# spi_cam.net
KiCad netlist of a schematic drawn in EAGLE
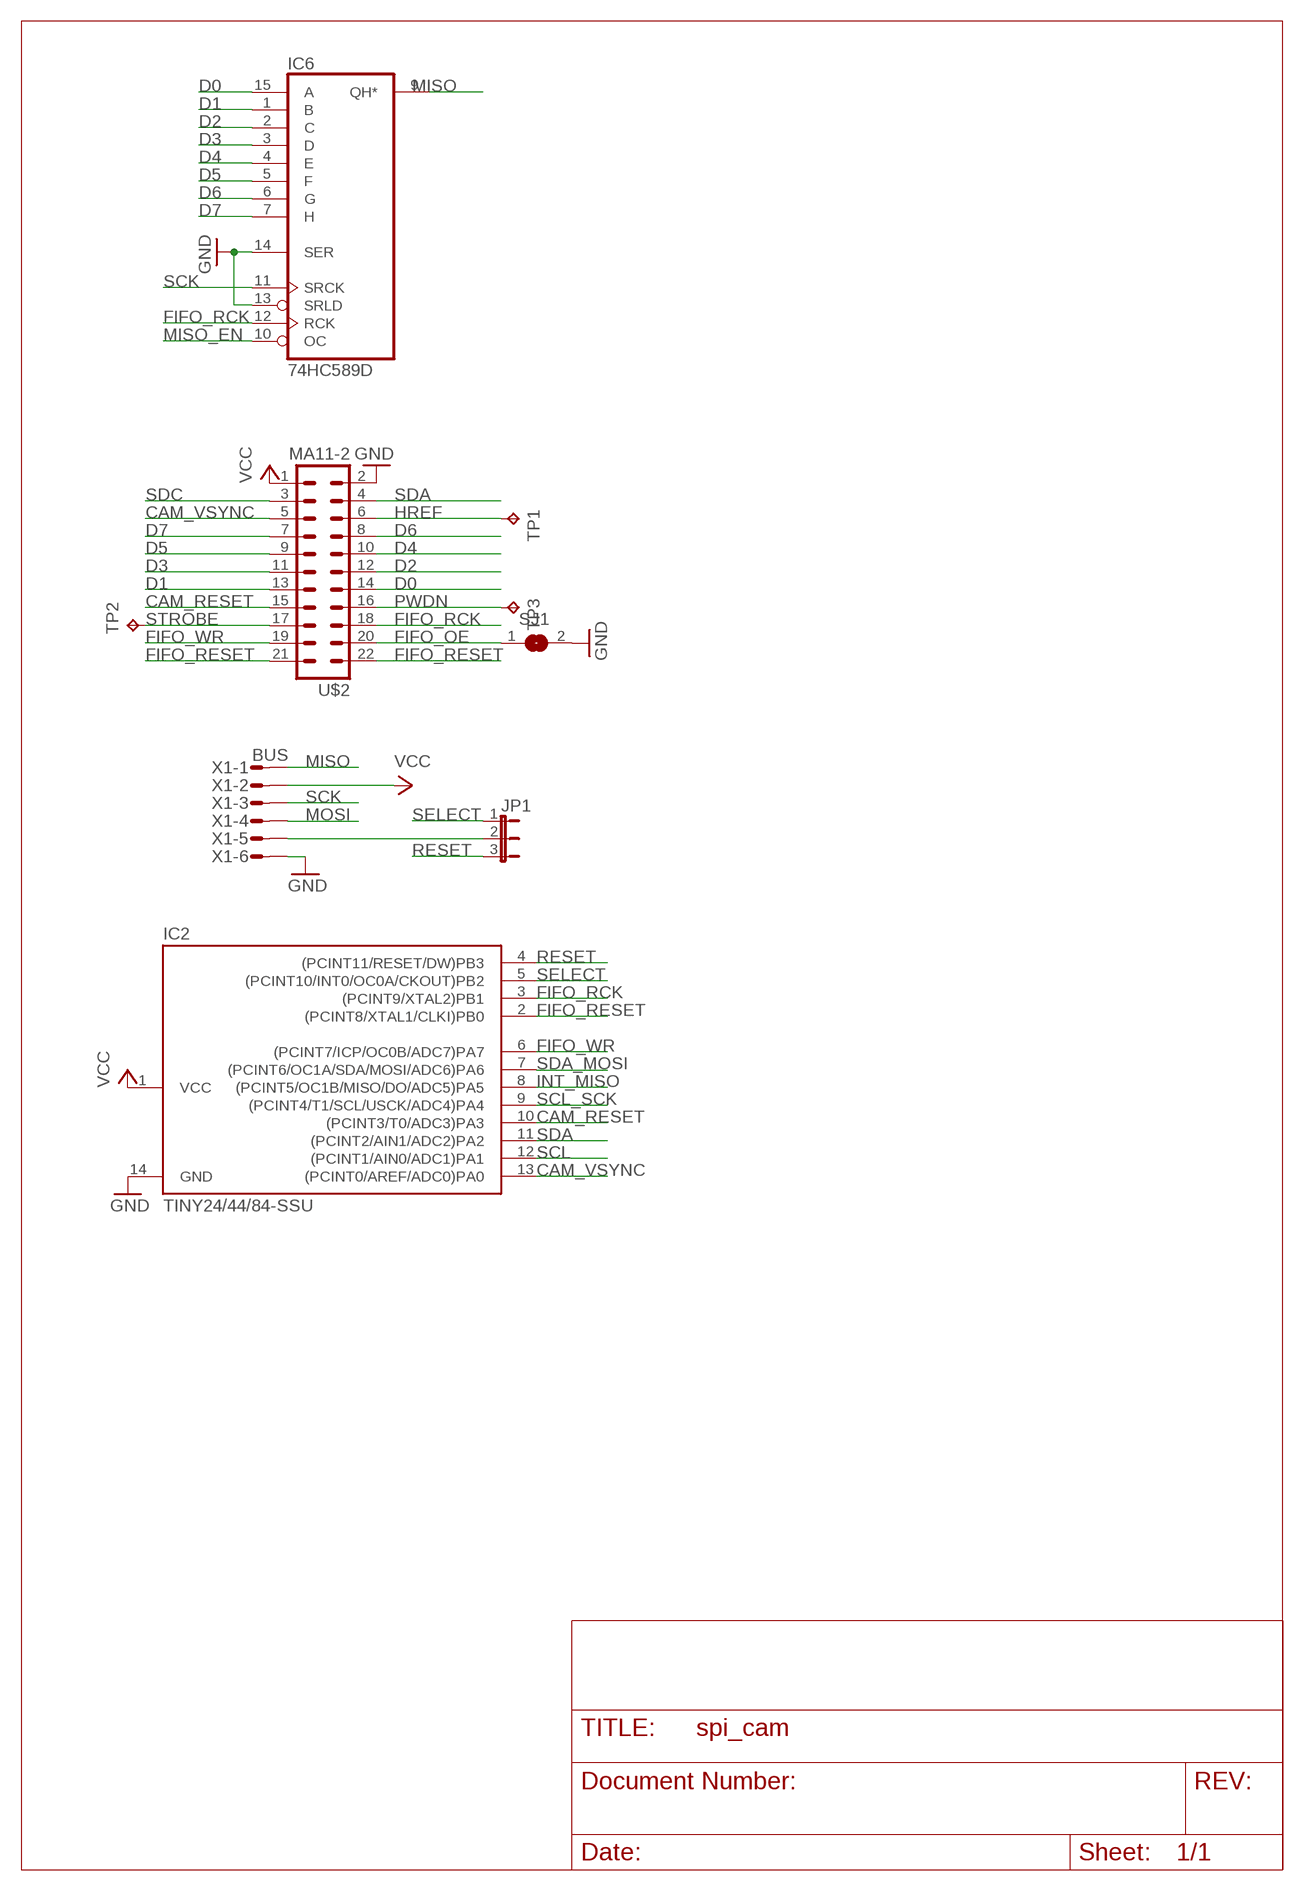
[diagram p0: schematic, sheet 1]

(export (version "E")
  (design (tool "Eeschema 10.0.6"))
  (components
    (comp (ref "IC2")
      (value "TINY24/44/84-SSU")
      (footprint "eagle-import:SOIC14")
      (libsource (lib "eagle-import") (part "TINY24/44/84-SSU"))
    )
    (comp (ref "IC6")
      (value "74HC589D")
      (footprint "eagle-import:SO16")
      (libsource (lib "eagle-import") (part "74589DHC"))
    )
    (comp (ref "JP1")
      (value "JP2E")
      (footprint "eagle-import:JP2")
      (libsource (lib "eagle-import") (part "JP2E"))
    )
    (comp (ref "SJ1") (value "SJ") (footprint "eagle-import:SJ") (libsource (lib "eagle-import") (part "SJ")))
    (comp (ref "TP1")
      (value "TPB1,27")
      (footprint "eagle-import:B1,27")
      (libsource (lib "eagle-import") (part "TPB1,27"))
    )
    (comp (ref "TP2")
      (value "TPB1,27")
      (footprint "eagle-import:B1,27")
      (libsource (lib "eagle-import") (part "TPB1,27"))
    )
    (comp (ref "TP3")
      (value "TPB1,27")
      (footprint "eagle-import:B1,27")
      (libsource (lib "eagle-import") (part "TPB1,27"))
    )
    (comp (ref "U$2")
      (value "MA11-2")
      (footprint "eagle-import:MA11-2")
      (libsource (lib "eagle-import") (part "MA11-2"))
    )
    (comp (ref "X1")
      (value "BUS")
      (footprint "eagle-import:MICROMATCH-6")
      (fields (field (name "MPN") "7-215464-6"))
      (libsource (lib "eagle-import") (part "MICROMATCH-6"))
    )
  )
  (nets
    (net (code "1") (name "/CAM_RESET") (class "Default")
      (node (ref "IC2") (pin "10") (pinfunction "(PCINT3/T0/ADC3)PA3_10") (pintype "bidirectional"))
      (node (ref "U$2") (pin "15") (pinfunction "15_15") (pintype "passive"))
    )
    (net (code "2") (name "/CAM_VSYNC") (class "Default")
      (node (ref "IC2") (pin "13") (pinfunction "(PCINT0/AREF/ADC0)PA0_13") (pintype "bidirectional"))
      (node (ref "U$2") (pin "5") (pinfunction "5_5") (pintype "passive"))
    )
    (net (code "3") (name "/D0") (class "Default")
      (node (ref "IC6") (pin "15") (pinfunction "A_15") (pintype "input"))
      (node (ref "U$2") (pin "14") (pinfunction "14_14") (pintype "passive"))
    )
    (net (code "4") (name "/D1") (class "Default")
      (node (ref "IC6") (pin "1") (pinfunction "B_1") (pintype "input"))
      (node (ref "U$2") (pin "13") (pinfunction "13_13") (pintype "passive"))
    )
    (net (code "5") (name "/D2") (class "Default")
      (node (ref "IC6") (pin "2") (pinfunction "C_2") (pintype "input"))
      (node (ref "U$2") (pin "12") (pinfunction "12_12") (pintype "passive"))
    )
    (net (code "6") (name "/D3") (class "Default")
      (node (ref "IC6") (pin "3") (pinfunction "D_3") (pintype "input"))
      (node (ref "U$2") (pin "11") (pinfunction "11_11") (pintype "passive"))
    )
    (net (code "7") (name "/D4") (class "Default")
      (node (ref "IC6") (pin "4") (pinfunction "E_4") (pintype "input"))
      (node (ref "U$2") (pin "10") (pinfunction "10_10") (pintype "passive"))
    )
    (net (code "8") (name "/D5") (class "Default")
      (node (ref "IC6") (pin "5") (pinfunction "F_5") (pintype "input"))
      (node (ref "U$2") (pin "9") (pinfunction "9_9") (pintype "passive"))
    )
    (net (code "9") (name "/D6") (class "Default")
      (node (ref "IC6") (pin "6") (pinfunction "G_6") (pintype "input"))
      (node (ref "U$2") (pin "8") (pinfunction "8_8") (pintype "passive"))
    )
    (net (code "10") (name "/D7") (class "Default")
      (node (ref "IC6") (pin "7") (pinfunction "H_7") (pintype "input"))
      (node (ref "U$2") (pin "7") (pinfunction "7_7") (pintype "passive"))
    )
    (net (code "11") (name "/FIFO_OE") (class "Default")
      (node (ref "SJ1") (pin "1") (pinfunction "1_1") (pintype "passive"))
      (node (ref "U$2") (pin "20") (pinfunction "20_20") (pintype "passive"))
    )
    (net (code "12") (name "/FIFO_RCK") (class "Default")
      (node (ref "IC2") (pin "3") (pinfunction "(PCINT9/XTAL2)PB1_3") (pintype "bidirectional"))
      (node (ref "IC6") (pin "12") (pinfunction "RCK_12") (pintype "input"))
      (node (ref "U$2") (pin "18") (pinfunction "18_18") (pintype "passive"))
    )
    (net (code "13") (name "/FIFO_RESET") (class "Default")
      (node (ref "IC2") (pin "2") (pinfunction "(PCINT8/XTAL1/CLKI)PB0_2") (pintype "bidirectional"))
      (node (ref "U$2") (pin "21") (pinfunction "21_21") (pintype "passive"))
      (node (ref "U$2") (pin "22") (pinfunction "22_22") (pintype "passive"))
    )
    (net (code "14") (name "/FIFO_WR") (class "Default")
      (node (ref "IC2") (pin "6") (pinfunction "(PCINT7/ICP/OC0B/ADC7)PA7_6") (pintype "bidirectional"))
      (node (ref "U$2") (pin "19") (pinfunction "19_19") (pintype "passive"))
    )
    (net (code "15") (name "/HREF") (class "Default")
      (node (ref "TP1") (pin "TP") (pinfunction "TP_TP") (pintype "input"))
      (node (ref "U$2") (pin "6") (pinfunction "6_6") (pintype "passive"))
    )
    (net (code "16") (name "/INT_MISO") (class "Default")
      (node (ref "IC2") (pin "8") (pinfunction "(PCINT5/OC1B/MISO/DO/ADC5)PA5_8") (pintype "bidirectional"))
    )
    (net (code "17") (name "/MISO") (class "Default")
      (node (ref "IC6") (pin "9") (pinfunction "QH*_9") (pintype "tri_state"))
      (node (ref "X1") (pin "1") (pinfunction "S_1") (pintype "passive"))
    )
    (net (code "18") (name "/MISO_EN") (class "Default")
      (node (ref "IC6") (pin "10") (pinfunction "OC_10") (pintype "input"))
    )
    (net (code "19") (name "/MOSI") (class "Default")
      (node (ref "X1") (pin "4") (pinfunction "S_4") (pintype "passive"))
    )
    (net (code "20") (name "/PWDN") (class "Default")
      (node (ref "TP3") (pin "TP") (pinfunction "TP_TP") (pintype "input"))
      (node (ref "U$2") (pin "16") (pinfunction "16_16") (pintype "passive"))
    )
    (net (code "21") (name "/RESET") (class "Default")
      (node (ref "IC2") (pin "4") (pinfunction "(PCINT11/RESET/DW)PB3_4") (pintype "bidirectional"))
      (node (ref "JP1") (pin "3") (pinfunction "3_3") (pintype "passive"))
    )
    (net (code "22") (name "/SCK") (class "Default")
      (node (ref "IC6") (pin "11") (pinfunction "SRCK_11") (pintype "input"))
      (node (ref "X1") (pin "3") (pinfunction "S_3") (pintype "passive"))
    )
    (net (code "23") (name "/SCL") (class "Default")
      (node (ref "IC2") (pin "12") (pinfunction "(PCINT1/AIN0/ADC1)PA1_12") (pintype "bidirectional"))
    )
    (net (code "24") (name "/SCL_SCK") (class "Default")
      (node (ref "IC2") (pin "9") (pinfunction "(PCINT4/T1/SCL/USCK/ADC4)PA4_9") (pintype "bidirectional"))
    )
    (net (code "25") (name "/SDA") (class "Default")
      (node (ref "IC2") (pin "11") (pinfunction "(PCINT2/AIN1/ADC2)PA2_11") (pintype "bidirectional"))
      (node (ref "U$2") (pin "4") (pinfunction "4_4") (pintype "passive"))
    )
    (net (code "26") (name "/SDA_MOSI") (class "Default")
      (node (ref "IC2") (pin "7") (pinfunction "(PCINT6/OC1A/SDA/MOSI/ADC6)PA6_7") (pintype "bidirectional"))
    )
    (net (code "27") (name "/SDC") (class "Default")
      (node (ref "U$2") (pin "3") (pinfunction "3_3") (pintype "passive"))
    )
    (net (code "28") (name "/SELECT") (class "Default")
      (node (ref "IC2") (pin "5") (pinfunction "(PCINT10/INT0/OC0A/CKOUT)PB2_5") (pintype "bidirectional"))
      (node (ref "JP1") (pin "1") (pinfunction "1_1") (pintype "passive"))
    )
    (net (code "29") (name "/STROBE") (class "Default")
      (node (ref "TP2") (pin "TP") (pinfunction "TP_TP") (pintype "input"))
      (node (ref "U$2") (pin "17") (pinfunction "17_17") (pintype "passive"))
    )
    (net (code "30") (name "GND") (class "Default")
      (node (ref "IC2") (pin "14") (pinfunction "GND_14") (pintype "power_in"))
      (node (ref "IC6") (pin "13") (pinfunction "SRLD_13") (pintype "input"))
      (node (ref "IC6") (pin "14") (pinfunction "SER_14") (pintype "input"))
      (node (ref "SJ1") (pin "2") (pinfunction "2_2") (pintype "passive"))
      (node (ref "U$2") (pin "2") (pinfunction "2_2") (pintype "passive"))
      (node (ref "X1") (pin "6") (pinfunction "S_6") (pintype "passive"))
    )
    (net (code "31") (name "Net-(X1E-S)") (class "Default")
      (node (ref "JP1") (pin "2") (pinfunction "2_2") (pintype "passive"))
      (node (ref "X1") (pin "5") (pinfunction "S_5") (pintype "passive"))
    )
    (net (code "32") (name "VCC") (class "Default")
      (node (ref "IC2") (pin "1") (pinfunction "VCC_1") (pintype "power_in"))
      (node (ref "U$2") (pin "1") (pinfunction "1_1") (pintype "passive"))
      (node (ref "X1") (pin "2") (pinfunction "S_2") (pintype "passive"))
    )
  )
)
